# DigiSporc_nano.net
KiCad netlist of a schematic drawn in EAGLE
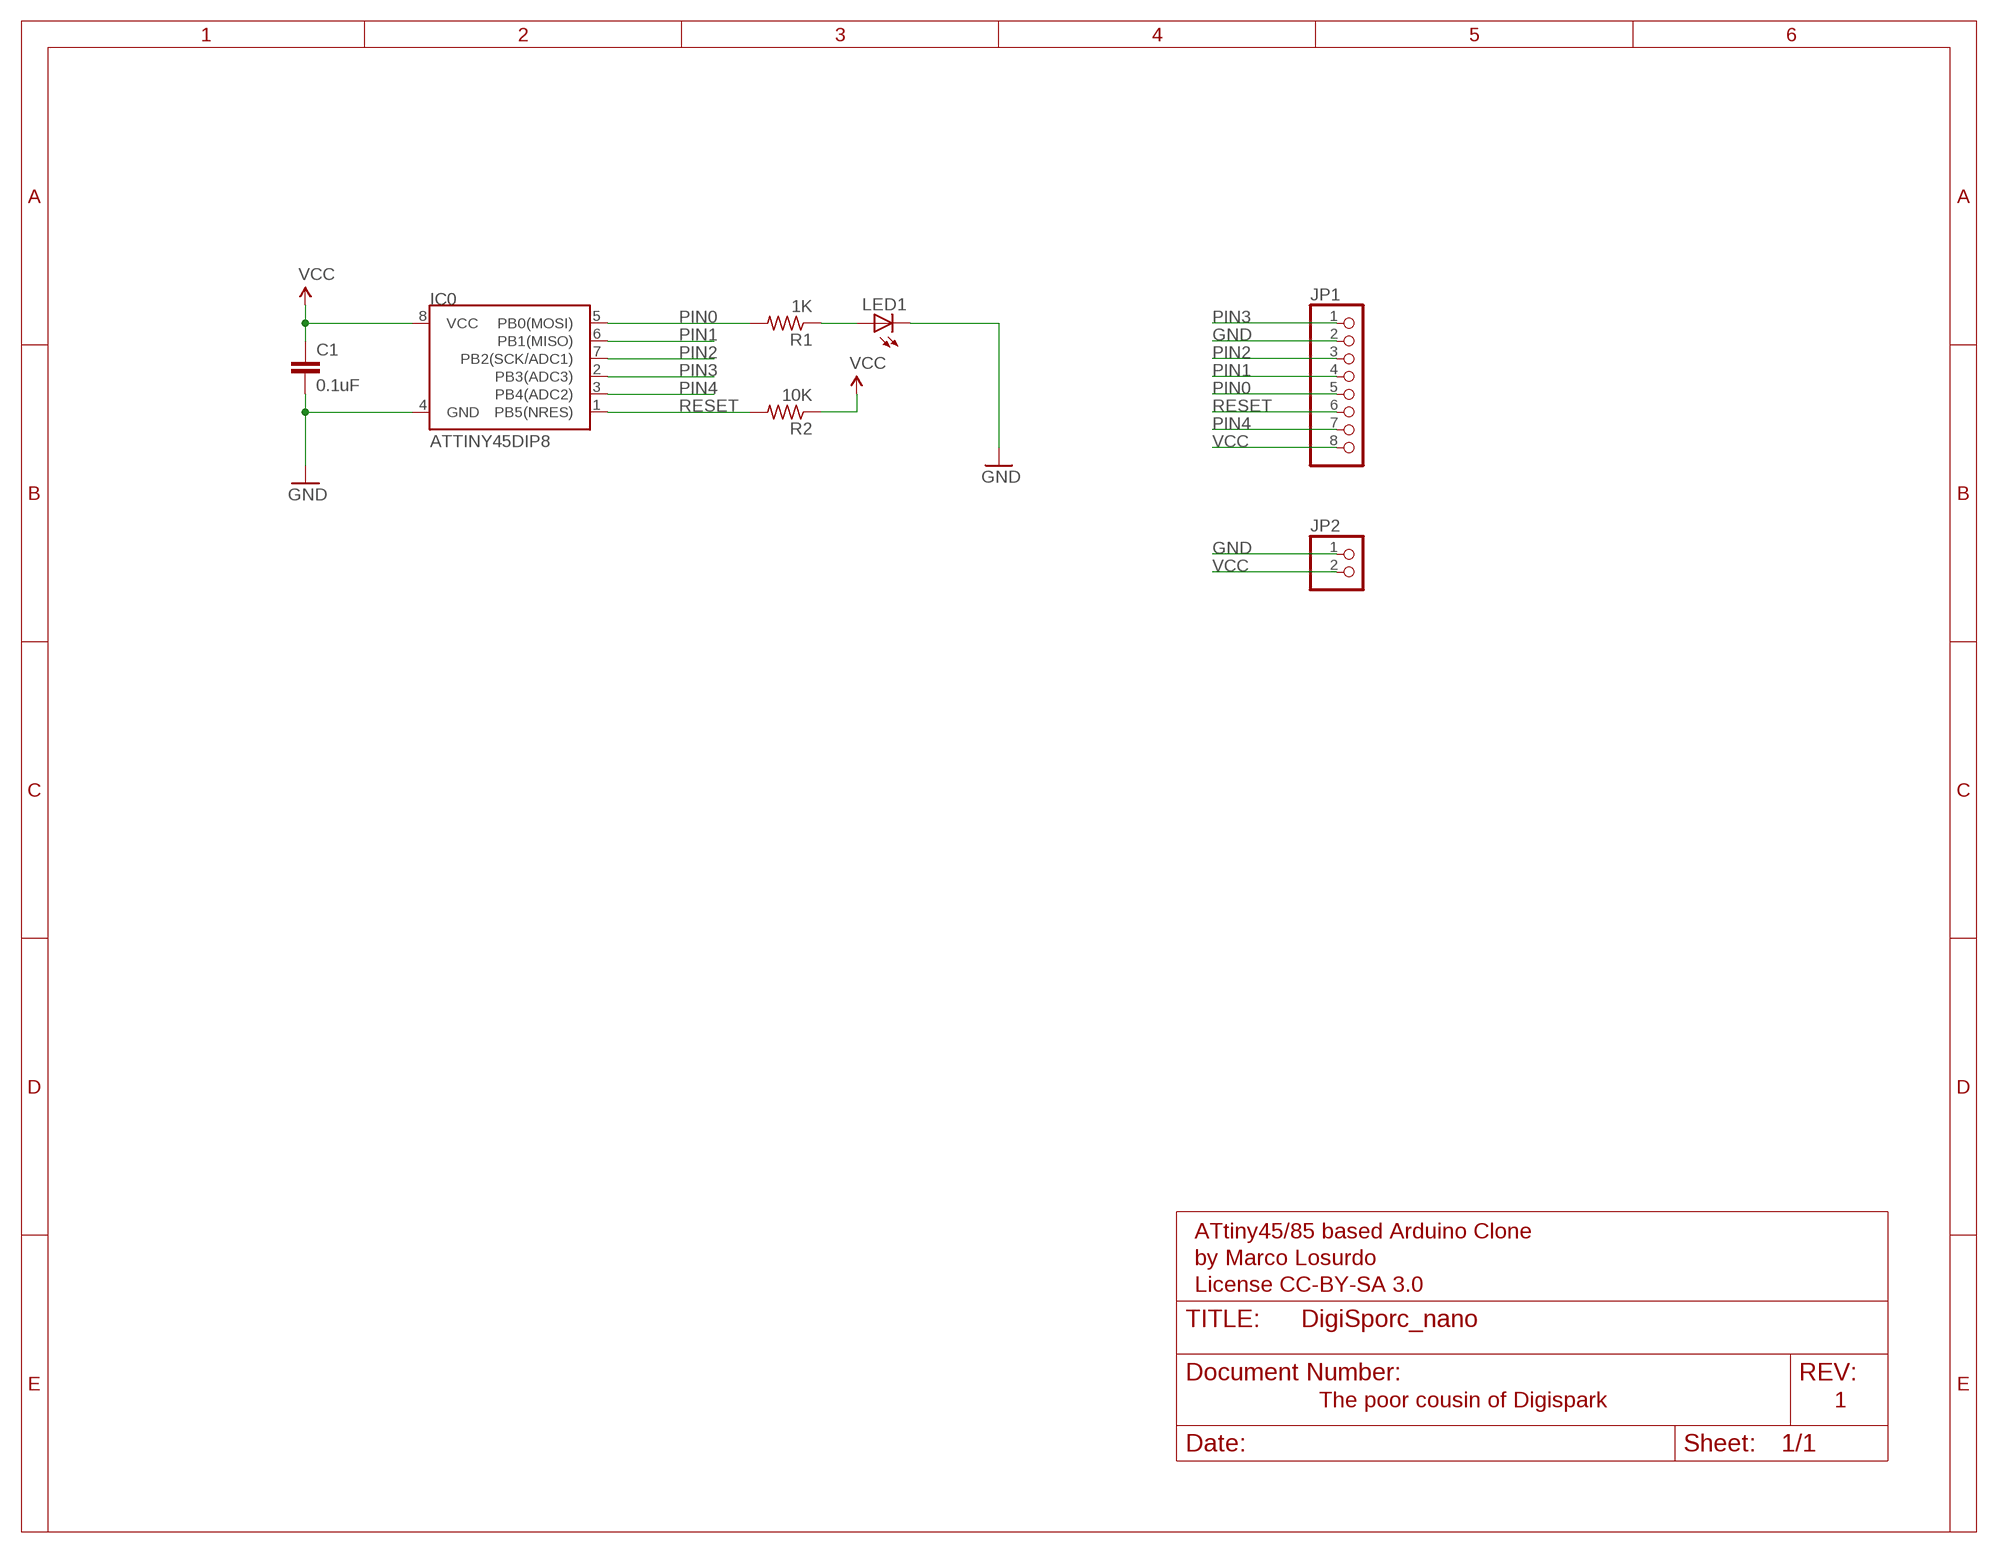
[diagram p0: schematic, sheet 1]

(export (version "E")
  (design (tool "Eeschema 10.0.6"))
  (components
    (comp (ref "C1")
      (value "0.1uF")
      (footprint "eagle-import:CAP-PTH-SMALL")
      (libsource (lib "eagle-import") (part "CAPPTH"))
    )
    (comp (ref "IC0")
      (value "ATTINY45DIP8")
      (footprint "eagle-import:DIP08")
      (libsource (lib "eagle-import") (part "ATTINY45DIP8"))
    )
    (comp (ref "JP1")
      (value "PINHD-1X8")
      (footprint "eagle-import:1X08")
      (libsource (lib "eagle-import") (part "PINHD-1X8"))
    )
    (comp (ref "JP2")
      (value "PINHD-1X2")
      (footprint "eagle-import:1X02")
      (libsource (lib "eagle-import") (part "PINHD-1X2"))
    )
    (comp (ref "LED1")
      (value "LED3MM")
      (footprint "eagle-import:LED3MM")
      (libsource (lib "eagle-import") (part "LED3MM"))
    )
    (comp (ref "R1")
      (value "1K")
      (footprint "eagle-import:0204_7")
      (libsource (lib "eagle-import") (part "R-US_0204/7"))
    )
    (comp (ref "R2")
      (value "10K")
      (footprint "eagle-import:0204_7")
      (libsource (lib "eagle-import") (part "R-US_0204/7"))
    )
  )
  (nets
    (net (code "1") (name "/PIN0") (class "Default")
      (node (ref "IC0") (pin "5") (pinfunction "PB0(MOSI)_5") (pintype "bidirectional"))
      (node (ref "JP1") (pin "5") (pinfunction "5_5") (pintype "passive"))
      (node (ref "R1") (pin "2") (pinfunction "2_2") (pintype "passive"))
    )
    (net (code "2") (name "/PIN1") (class "Default")
      (node (ref "IC0") (pin "6") (pinfunction "PB1(MISO)_6") (pintype "bidirectional"))
      (node (ref "JP1") (pin "4") (pinfunction "4_4") (pintype "passive"))
    )
    (net (code "3") (name "/PIN2") (class "Default")
      (node (ref "IC0") (pin "7") (pinfunction "PB2(SCK/ADC1)_7") (pintype "bidirectional"))
      (node (ref "JP1") (pin "3") (pinfunction "3_3") (pintype "passive"))
    )
    (net (code "4") (name "/PIN3") (class "Default")
      (node (ref "IC0") (pin "2") (pinfunction "PB3(ADC3)_2") (pintype "bidirectional"))
      (node (ref "JP1") (pin "1") (pinfunction "1_1") (pintype "passive"))
    )
    (net (code "5") (name "/PIN4") (class "Default")
      (node (ref "IC0") (pin "3") (pinfunction "PB4(ADC2)_3") (pintype "bidirectional"))
      (node (ref "JP1") (pin "7") (pinfunction "7_7") (pintype "passive"))
    )
    (net (code "6") (name "/RESET") (class "Default")
      (node (ref "IC0") (pin "1") (pinfunction "PB5(NRES)_1") (pintype "bidirectional"))
      (node (ref "JP1") (pin "6") (pinfunction "6_6") (pintype "passive"))
      (node (ref "R2") (pin "2") (pinfunction "2_2") (pintype "passive"))
    )
    (net (code "7") (name "GND") (class "Default")
      (node (ref "C1") (pin "2") (pinfunction "2_2") (pintype "passive"))
      (node (ref "IC0") (pin "4") (pinfunction "GND_4") (pintype "bidirectional"))
      (node (ref "JP1") (pin "2") (pinfunction "2_2") (pintype "passive"))
      (node (ref "JP2") (pin "1") (pinfunction "1_1") (pintype "passive"))
      (node (ref "LED1") (pin "K") (pinfunction "C_K") (pintype "passive"))
    )
    (net (code "8") (name "Net-(LED1-PadA)") (class "Default")
      (node (ref "LED1") (pin "A") (pinfunction "A_A") (pintype "passive"))
      (node (ref "R1") (pin "1") (pinfunction "1_1") (pintype "passive"))
    )
    (net (code "9") (name "VCC") (class "Default")
      (node (ref "C1") (pin "1") (pinfunction "1_1") (pintype "passive"))
      (node (ref "IC0") (pin "8") (pinfunction "VCC_8") (pintype "bidirectional"))
      (node (ref "JP1") (pin "8") (pinfunction "8_8") (pintype "passive"))
      (node (ref "JP2") (pin "2") (pinfunction "2_2") (pintype "passive"))
      (node (ref "R2") (pin "1") (pinfunction "1_1") (pintype "passive"))
    )
  )
)
